# i2c_stuff.net
KiCad netlist of a schematic drawn in Altium Designer
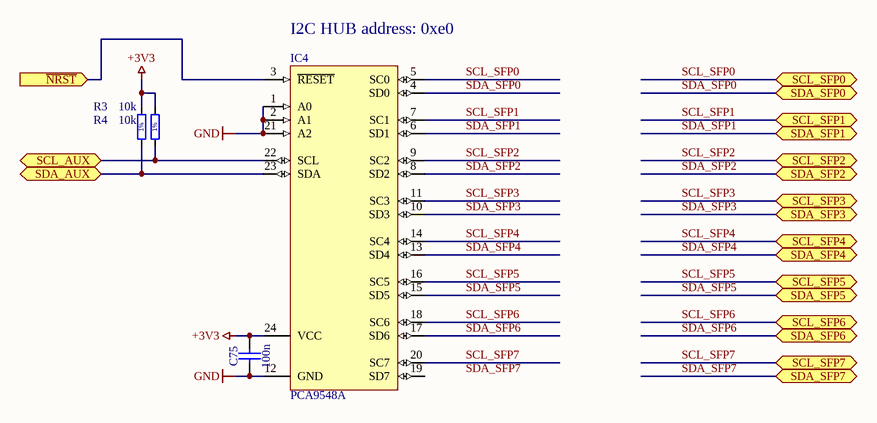
[diagram p0: i2c_stuff.SchDoc]

(export (version "E")
  (design (tool "Eeschema 10.0.6"))
  (components
    (comp (ref "C75")
      (value "100n")
      (footprint "CAPC1608X87N")
      (description "Non-polarised capacitor")
      (fields
        (field (name "PART NUMBER") "CC0603_100NF_50V_10%_X7R")
        (field (name "VOLTAGE") "50V")
        (field (name "AUTHOR") "CERN DEM JLC")
      )
      (libsource (lib "Capacitors") (part "Capacitor - non polarized"))
    )
    (comp (ref "IC4")
      (value "PCA9548A")
      (footprint "TSOP65P640-24AL")
      (description "1-to-8 I2C bus mux")
      (libsource (lib "wr_switch") (part "PCA9548A"))
    )
    (comp (ref "R3")
      (value "10k")
      (footprint "RESC1608X55N")
      (description "Resistor - 1%")
      (fields
        (field (name "PART NUMBER") "R0603_10K_1%_0.1W_100PPM")
        (field (name "POWER") "0.1W")
        (field (name "AUTHOR") "CERN DEM JLC")
      )
      (libsource (lib "Resistors") (part "Resistor - 1%"))
    )
    (comp (ref "R4")
      (value "10k")
      (footprint "RESC1608X55N")
      (description "Resistor - 1%")
      (fields
        (field (name "PART NUMBER") "R0603_10K_1%_0.1W_100PPM")
        (field (name "POWER") "0.1W")
        (field (name "AUTHOR") "CERN DEM JLC")
      )
      (libsource (lib "Resistors") (part "Resistor - 1%"))
    )
  )
  (nets
    (net (code "1") (name "+3V3") (class "Default")
      (node (ref "C75") (pin "2") (pinfunction "2_2") (pintype "passive"))
      (node (ref "IC4") (pin "24") (pinfunction "VCC_24") (pintype "power_in"))
      (node (ref "R3") (pin "2") (pinfunction "2_2") (pintype "passive"))
      (node (ref "R4") (pin "2") (pinfunction "2_2") (pintype "passive"))
    )
    (net (code "2") (name "/SCL_AUX") (class "Default")
      (node (ref "IC4") (pin "22") (pinfunction "SCL_22") (pintype "bidirectional"))
      (node (ref "R3") (pin "1") (pinfunction "1_1") (pintype "passive"))
    )
    (net (code "3") (name "/SCL_SFP0") (class "Default")
      (node (ref "IC4") (pin "5") (pinfunction "SC0_5") (pintype "bidirectional"))
    )
    (net (code "4") (name "/SCL_SFP1") (class "Default")
      (node (ref "IC4") (pin "7") (pinfunction "SC1_7") (pintype "bidirectional"))
    )
    (net (code "5") (name "/SCL_SFP2") (class "Default")
      (node (ref "IC4") (pin "9") (pinfunction "SC2_9") (pintype "bidirectional"))
    )
    (net (code "6") (name "/SCL_SFP3") (class "Default")
      (node (ref "IC4") (pin "11") (pinfunction "SC3_11") (pintype "bidirectional"))
    )
    (net (code "7") (name "/SCL_SFP4") (class "Default")
      (node (ref "IC4") (pin "14") (pinfunction "SC4_14") (pintype "bidirectional"))
    )
    (net (code "8") (name "/SCL_SFP5") (class "Default")
      (node (ref "IC4") (pin "16") (pinfunction "SC5_16") (pintype "bidirectional"))
    )
    (net (code "9") (name "/SCL_SFP6") (class "Default")
      (node (ref "IC4") (pin "18") (pinfunction "SC6_18") (pintype "bidirectional"))
    )
    (net (code "10") (name "/SCL_SFP7") (class "Default")
      (node (ref "IC4") (pin "20") (pinfunction "SC7_20") (pintype "bidirectional"))
    )
    (net (code "11") (name "/SDA_AUX") (class "Default")
      (node (ref "IC4") (pin "23") (pinfunction "SDA_23") (pintype "bidirectional"))
      (node (ref "R4") (pin "1") (pinfunction "1_1") (pintype "passive"))
    )
    (net (code "12") (name "/SDA_SFP0") (class "Default")
      (node (ref "IC4") (pin "4") (pinfunction "SD0_4") (pintype "bidirectional"))
    )
    (net (code "13") (name "/SDA_SFP1") (class "Default")
      (node (ref "IC4") (pin "6") (pinfunction "SD1_6") (pintype "bidirectional"))
    )
    (net (code "14") (name "/SDA_SFP2") (class "Default")
      (node (ref "IC4") (pin "8") (pinfunction "SD2_8") (pintype "bidirectional"))
    )
    (net (code "15") (name "/SDA_SFP3") (class "Default")
      (node (ref "IC4") (pin "10") (pinfunction "SD3_10") (pintype "bidirectional"))
    )
    (net (code "16") (name "/SDA_SFP4") (class "Default")
      (node (ref "IC4") (pin "13") (pinfunction "SD4_13") (pintype "bidirectional"))
    )
    (net (code "17") (name "/SDA_SFP5") (class "Default")
      (node (ref "IC4") (pin "15") (pinfunction "SD5_15") (pintype "bidirectional"))
    )
    (net (code "18") (name "/SDA_SFP6") (class "Default")
      (node (ref "IC4") (pin "17") (pinfunction "SD6_17") (pintype "bidirectional"))
    )
    (net (code "20") (name "/~{NRST}") (class "Default")
      (node (ref "IC4") (pin "3") (pinfunction "~{RESET}_3") (pintype "input"))
    )
    (net (code "21") (name "GND") (class "Default")
      (node (ref "C75") (pin "1") (pinfunction "1_1") (pintype "passive"))
      (node (ref "IC4") (pin "1") (pinfunction "A0_1") (pintype "input"))
      (node (ref "IC4") (pin "12") (pinfunction "GND_12") (pintype "power_in"))
      (node (ref "IC4") (pin "2") (pinfunction "A1_2") (pintype "input"))
      (node (ref "IC4") (pin "21") (pinfunction "A2_21") (pintype "input"))
    )
    (net (code "22") (name "unconnected-(IC4-SD7-Pad19)") (class "Default")
      (node (ref "IC4") (pin "19") (pinfunction "SD7_19") (pintype "bidirectional"))
    )
  )
)
